# HackflightBrushed.net
KiCad netlist of a schematic drawn in EAGLE
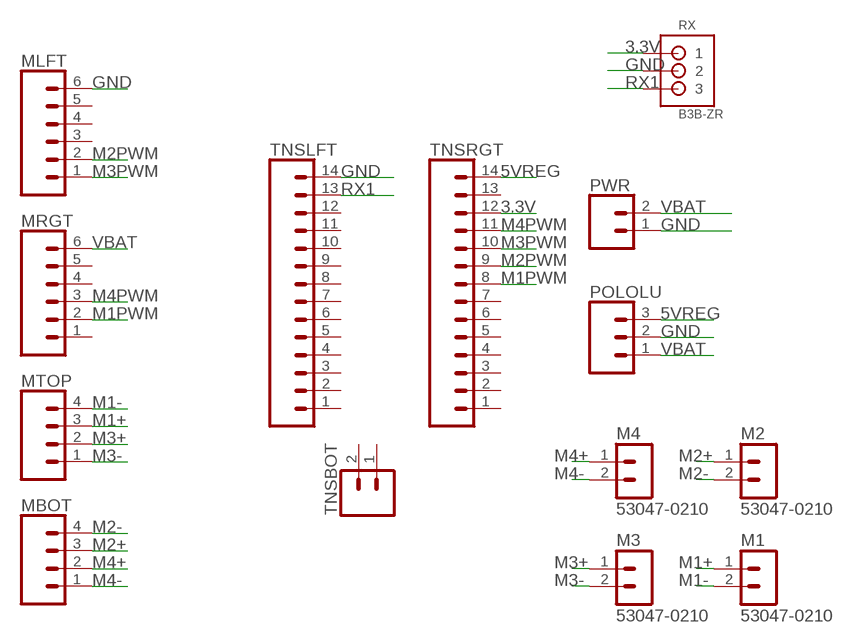
[diagram p0: schematic, sheet 1]

(export (version "E")
  (design (tool "Eeschema 10.0.6"))
  (components
    (comp (ref "M1")
      (value "53047-0210")
      (footprint "eagle-import:53047-0210")
      (libsource (lib "eagle-import") (part "53047-0210"))
    )
    (comp (ref "M2")
      (value "53047-0210")
      (footprint "eagle-import:53047-0210")
      (libsource (lib "eagle-import") (part "53047-0210"))
    )
    (comp (ref "M3")
      (value "53047-0210")
      (footprint "eagle-import:53047-0210")
      (libsource (lib "eagle-import") (part "53047-0210"))
    )
    (comp (ref "M4")
      (value "53047-0210")
      (footprint "eagle-import:53047-0210")
      (libsource (lib "eagle-import") (part "53047-0210"))
    )
    (comp (ref "MBOT")
      (value "CONN_04")
      (footprint "eagle-import:1X04")
      (libsource (lib "eagle-import") (part "CONN_04"))
    )
    (comp (ref "MLFT")
      (value "CONN_06NO_SILK_FEMALE_PTH")
      (footprint "eagle-import:1X06_NO_SILK")
      (libsource (lib "eagle-import") (part "CONN_06NO_SILK_FEMALE_PTH"))
    )
    (comp (ref "MRGT")
      (value "CONN_06NO_SILK_FEMALE_PTH")
      (footprint "eagle-import:1X06_NO_SILK")
      (libsource (lib "eagle-import") (part "CONN_06NO_SILK_FEMALE_PTH"))
    )
    (comp (ref "MTOP")
      (value "CONN_04")
      (footprint "eagle-import:1X04")
      (libsource (lib "eagle-import") (part "CONN_04"))
    )
    (comp (ref "POLOLU")
      (value "CONN_03")
      (footprint "eagle-import:1X03")
      (libsource (lib "eagle-import") (part "CONN_03"))
    )
    (comp (ref "PWR")
      (value "CONN_02")
      (footprint "eagle-import:1X02")
      (libsource (lib "eagle-import") (part "CONN_02"))
    )
    (comp (ref "RX")
      (value "B3B-ZR")
      (footprint "eagle-import:B3B-ZR")
      (libsource (lib "eagle-import") (part "B3B-ZR"))
    )
    (comp (ref "TNSBOT")
      (value "CONN_02")
      (footprint "eagle-import:1X02")
      (libsource (lib "eagle-import") (part "CONN_02"))
    )
    (comp (ref "TNSLFT")
      (value "CONN_14")
      (footprint "eagle-import:1X14")
      (libsource (lib "eagle-import") (part "CONN_14"))
    )
    (comp (ref "TNSRGT")
      (value "CONN_14")
      (footprint "eagle-import:1X14")
      (libsource (lib "eagle-import") (part "CONN_14"))
    )
  )
  (nets
    (net (code "1") (name "/3.3V") (class "Default")
      (node (ref "RX") (pin "1") (pinfunction "1_1") (pintype "bidirectional"))
      (node (ref "TNSRGT") (pin "12") (pinfunction "12_12") (pintype "passive"))
    )
    (net (code "2") (name "/5VREG") (class "Default")
      (node (ref "POLOLU") (pin "3") (pinfunction "3_3") (pintype "passive"))
      (node (ref "TNSRGT") (pin "14") (pinfunction "14_14") (pintype "passive"))
    )
    (net (code "3") (name "/GND") (class "Default")
      (node (ref "MLFT") (pin "6") (pinfunction "6_6") (pintype "passive"))
      (node (ref "POLOLU") (pin "2") (pinfunction "2_2") (pintype "passive"))
      (node (ref "PWR") (pin "1") (pinfunction "1_1") (pintype "passive"))
      (node (ref "RX") (pin "2") (pinfunction "2_2") (pintype "bidirectional"))
      (node (ref "TNSLFT") (pin "14") (pinfunction "14_14") (pintype "passive"))
    )
    (net (code "4") (name "/M1+") (class "Default")
      (node (ref "M1") (pin "1") (pinfunction "1_1") (pintype "passive"))
      (node (ref "MTOP") (pin "3") (pinfunction "3_3") (pintype "passive"))
    )
    (net (code "5") (name "/M1-") (class "Default")
      (node (ref "M1") (pin "2") (pinfunction "2_2") (pintype "passive"))
      (node (ref "MTOP") (pin "4") (pinfunction "4_4") (pintype "passive"))
    )
    (net (code "6") (name "/M1PWM") (class "Default")
      (node (ref "MRGT") (pin "2") (pinfunction "2_2") (pintype "passive"))
      (node (ref "TNSRGT") (pin "8") (pinfunction "8_8") (pintype "passive"))
    )
    (net (code "7") (name "/M2+") (class "Default")
      (node (ref "M2") (pin "1") (pinfunction "1_1") (pintype "passive"))
      (node (ref "MBOT") (pin "3") (pinfunction "3_3") (pintype "passive"))
    )
    (net (code "8") (name "/M2-") (class "Default")
      (node (ref "M2") (pin "2") (pinfunction "2_2") (pintype "passive"))
      (node (ref "MBOT") (pin "4") (pinfunction "4_4") (pintype "passive"))
    )
    (net (code "9") (name "/M2PWM") (class "Default")
      (node (ref "MLFT") (pin "2") (pinfunction "2_2") (pintype "passive"))
      (node (ref "TNSRGT") (pin "9") (pinfunction "9_9") (pintype "passive"))
    )
    (net (code "10") (name "/M3+") (class "Default")
      (node (ref "M3") (pin "1") (pinfunction "1_1") (pintype "passive"))
      (node (ref "MTOP") (pin "2") (pinfunction "2_2") (pintype "passive"))
    )
    (net (code "11") (name "/M3-") (class "Default")
      (node (ref "M3") (pin "2") (pinfunction "2_2") (pintype "passive"))
      (node (ref "MTOP") (pin "1") (pinfunction "1_1") (pintype "passive"))
    )
    (net (code "12") (name "/M3PWM") (class "Default")
      (node (ref "MLFT") (pin "1") (pinfunction "1_1") (pintype "passive"))
      (node (ref "TNSRGT") (pin "10") (pinfunction "10_10") (pintype "passive"))
    )
    (net (code "13") (name "/M4+") (class "Default")
      (node (ref "M4") (pin "1") (pinfunction "1_1") (pintype "passive"))
      (node (ref "MBOT") (pin "2") (pinfunction "2_2") (pintype "passive"))
    )
    (net (code "14") (name "/M4-") (class "Default")
      (node (ref "M4") (pin "2") (pinfunction "2_2") (pintype "passive"))
      (node (ref "MBOT") (pin "1") (pinfunction "1_1") (pintype "passive"))
    )
    (net (code "15") (name "/M4PWM") (class "Default")
      (node (ref "MRGT") (pin "3") (pinfunction "3_3") (pintype "passive"))
      (node (ref "TNSRGT") (pin "11") (pinfunction "11_11") (pintype "passive"))
    )
    (net (code "16") (name "/RX1") (class "Default")
      (node (ref "RX") (pin "3") (pinfunction "3_3") (pintype "bidirectional"))
      (node (ref "TNSLFT") (pin "13") (pinfunction "13_13") (pintype "passive"))
    )
    (net (code "17") (name "/VBAT") (class "Default")
      (node (ref "MRGT") (pin "6") (pinfunction "6_6") (pintype "passive"))
      (node (ref "POLOLU") (pin "1") (pinfunction "1_1") (pintype "passive"))
      (node (ref "PWR") (pin "2") (pinfunction "2_2") (pintype "passive"))
    )
    (net (code "18") (name "unconnected-(MLFT-Pad3)") (class "Default")
      (node (ref "MLFT") (pin "3") (pinfunction "3_3") (pintype "passive"))
    )
    (net (code "19") (name "unconnected-(MLFT-Pad4)") (class "Default")
      (node (ref "MLFT") (pin "4") (pinfunction "4_4") (pintype "passive"))
    )
    (net (code "20") (name "unconnected-(MLFT-Pad5)") (class "Default")
      (node (ref "MLFT") (pin "5") (pinfunction "5_5") (pintype "passive"))
    )
    (net (code "21") (name "unconnected-(MRGT-Pad1)") (class "Default")
      (node (ref "MRGT") (pin "1") (pinfunction "1_1") (pintype "passive"))
    )
    (net (code "22") (name "unconnected-(MRGT-Pad4)") (class "Default")
      (node (ref "MRGT") (pin "4") (pinfunction "4_4") (pintype "passive"))
    )
    (net (code "23") (name "unconnected-(MRGT-Pad5)") (class "Default")
      (node (ref "MRGT") (pin "5") (pinfunction "5_5") (pintype "passive"))
    )
    (net (code "24") (name "unconnected-(TNSBOT-Pad1)") (class "Default")
      (node (ref "TNSBOT") (pin "1") (pinfunction "1_1") (pintype "passive"))
    )
    (net (code "25") (name "unconnected-(TNSBOT-Pad2)") (class "Default")
      (node (ref "TNSBOT") (pin "2") (pinfunction "2_2") (pintype "passive"))
    )
    (net (code "26") (name "unconnected-(TNSLFT-Pad1)") (class "Default")
      (node (ref "TNSLFT") (pin "1") (pinfunction "1_1") (pintype "passive"))
    )
    (net (code "27") (name "unconnected-(TNSLFT-Pad2)") (class "Default")
      (node (ref "TNSLFT") (pin "2") (pinfunction "2_2") (pintype "passive"))
    )
    (net (code "28") (name "unconnected-(TNSLFT-Pad3)") (class "Default")
      (node (ref "TNSLFT") (pin "3") (pinfunction "3_3") (pintype "passive"))
    )
    (net (code "29") (name "unconnected-(TNSLFT-Pad4)") (class "Default")
      (node (ref "TNSLFT") (pin "4") (pinfunction "4_4") (pintype "passive"))
    )
    (net (code "30") (name "unconnected-(TNSLFT-Pad5)") (class "Default")
      (node (ref "TNSLFT") (pin "5") (pinfunction "5_5") (pintype "passive"))
    )
    (net (code "31") (name "unconnected-(TNSLFT-Pad6)") (class "Default")
      (node (ref "TNSLFT") (pin "6") (pinfunction "6_6") (pintype "passive"))
    )
    (net (code "32") (name "unconnected-(TNSLFT-Pad7)") (class "Default")
      (node (ref "TNSLFT") (pin "7") (pinfunction "7_7") (pintype "passive"))
    )
    (net (code "33") (name "unconnected-(TNSLFT-Pad8)") (class "Default")
      (node (ref "TNSLFT") (pin "8") (pinfunction "8_8") (pintype "passive"))
    )
    (net (code "34") (name "unconnected-(TNSLFT-Pad9)") (class "Default")
      (node (ref "TNSLFT") (pin "9") (pinfunction "9_9") (pintype "passive"))
    )
    (net (code "35") (name "unconnected-(TNSLFT-Pad10)") (class "Default")
      (node (ref "TNSLFT") (pin "10") (pinfunction "10_10") (pintype "passive"))
    )
    (net (code "36") (name "unconnected-(TNSLFT-Pad11)") (class "Default")
      (node (ref "TNSLFT") (pin "11") (pinfunction "11_11") (pintype "passive"))
    )
    (net (code "37") (name "unconnected-(TNSLFT-Pad12)") (class "Default")
      (node (ref "TNSLFT") (pin "12") (pinfunction "12_12") (pintype "passive"))
    )
    (net (code "38") (name "unconnected-(TNSRGT-Pad1)") (class "Default")
      (node (ref "TNSRGT") (pin "1") (pinfunction "1_1") (pintype "passive"))
    )
    (net (code "39") (name "unconnected-(TNSRGT-Pad2)") (class "Default")
      (node (ref "TNSRGT") (pin "2") (pinfunction "2_2") (pintype "passive"))
    )
    (net (code "40") (name "unconnected-(TNSRGT-Pad3)") (class "Default")
      (node (ref "TNSRGT") (pin "3") (pinfunction "3_3") (pintype "passive"))
    )
    (net (code "41") (name "unconnected-(TNSRGT-Pad4)") (class "Default")
      (node (ref "TNSRGT") (pin "4") (pinfunction "4_4") (pintype "passive"))
    )
    (net (code "42") (name "unconnected-(TNSRGT-Pad5)") (class "Default")
      (node (ref "TNSRGT") (pin "5") (pinfunction "5_5") (pintype "passive"))
    )
    (net (code "43") (name "unconnected-(TNSRGT-Pad6)") (class "Default")
      (node (ref "TNSRGT") (pin "6") (pinfunction "6_6") (pintype "passive"))
    )
    (net (code "44") (name "unconnected-(TNSRGT-Pad7)") (class "Default")
      (node (ref "TNSRGT") (pin "7") (pinfunction "7_7") (pintype "passive"))
    )
    (net (code "45") (name "unconnected-(TNSRGT-Pad13)") (class "Default")
      (node (ref "TNSRGT") (pin "13") (pinfunction "13_13") (pintype "passive"))
    )
  )
)
